# Astavel_and_Monostable_Clock_Circuit_-_2.net
KiCad netlist of a schematic drawn in Altium Designer
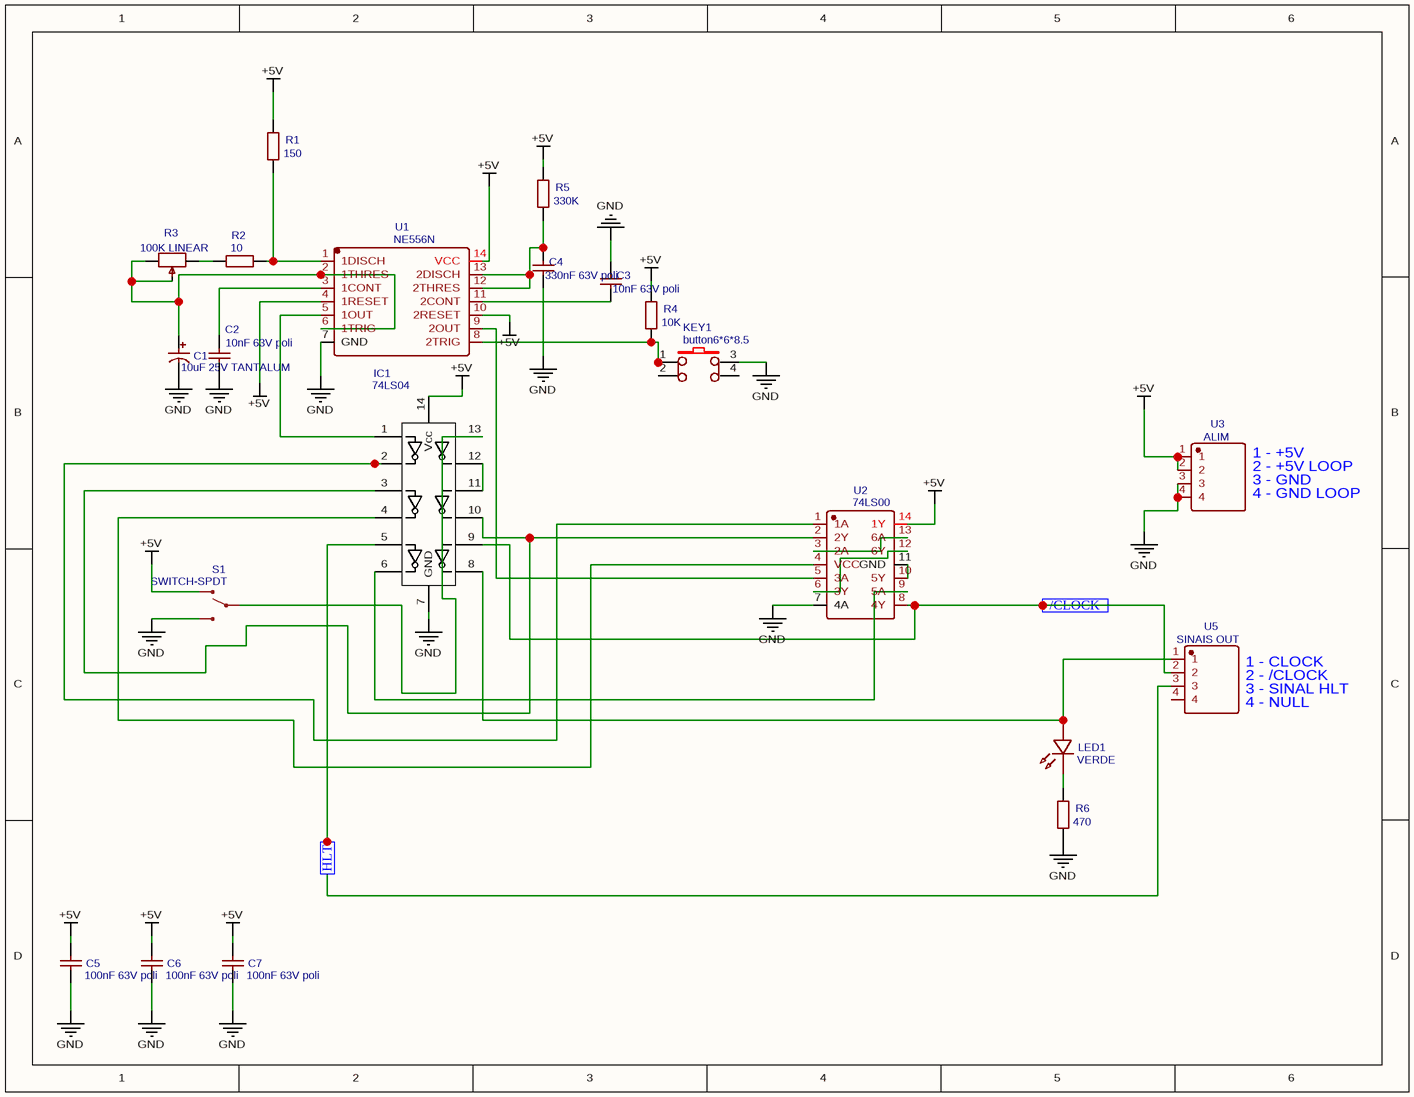
[diagram p0: Astavel and Monostable Clock Circuit - 2.0_2021-10-20.schdoc]

(export (version "E")
  (design (tool "Eeschema 10.0.6"))
  (components
    (comp (ref "C1")
      (value "10uF 25V TANTALUM")
      (fields
        (field (name "BOM_MANUFACTURER PART") "SK100M035B070A")
        (field (name "BOM_SUPPLIER PART") "C62931")
      )
      (libsource (lib "altium-import") (part "root_3_10uF 25V TANTALUM_"))
    )
    (comp (ref "C2")
      (value "10nF 63V poli")
      (fields
        (field (name "BOM_MANUFACTURER PART") "0.01uF(103) 100V")
        (field (name "BOM_SUPPLIER PART") "C10722")
      )
      (libsource (lib "altium-import") (part "root_3_10nF 63V poli_"))
    )
    (comp (ref "C3")
      (value "10nF 63V poli")
      (fields
        (field (name "BOM_MANUFACTURER PART") "0.01uF(103) 100V")
        (field (name "BOM_SUPPLIER PART") "C10722")
      )
      (libsource (lib "altium-import") (part "root_3_10nF 63V poli_"))
    )
    (comp (ref "C4")
      (value "330nF 63V poli")
      (fields
        (field (name "BOM_MANUFACTURER PART") "0.01uF(103) 100V")
        (field (name "BOM_SUPPLIER PART") "C10722")
      )
      (libsource (lib "altium-import") (part "root_3_330nF 63V poli_"))
    )
    (comp (ref "C5")
      (value "100nF 63V poli")
      (fields
        (field (name "BOM_MANUFACTURER PART") "0.01uF(103) 100V")
        (field (name "BOM_SUPPLIER PART") "C10722")
      )
      (libsource (lib "altium-import") (part "root_3_100nF 63V poli_"))
    )
    (comp (ref "C6")
      (value "100nF 63V poli")
      (fields
        (field (name "BOM_MANUFACTURER PART") "0.01uF(103) 100V")
        (field (name "BOM_SUPPLIER PART") "C10722")
      )
      (libsource (lib "altium-import") (part "root_3_100nF 63V poli_"))
    )
    (comp (ref "C7")
      (value "100nF 63V poli")
      (fields
        (field (name "BOM_MANUFACTURER PART") "0.01uF(103) 100V")
        (field (name "BOM_SUPPLIER PART") "C10722")
      )
      (libsource (lib "altium-import") (part "root_3_100nF 63V poli_"))
    )
    (comp (ref "IC1")
      (value "74LS04")
      (fields (field (name "CONTRIBUTOR") "keyboardjunkie"))
      (libsource (lib "altium-import") (part "root_0_74LS04_"))
    )
    (comp (ref "KEY1")
      (value "button6*6*8.5")
      (fields (field (name "BOM_SUPPLIER PART") "C59980"))
      (libsource (lib "altium-import") (part "root_0_button6*6*8.5_"))
    )
    (comp (ref "LED1")
      (value "VERDE")
      (fields
        (field (name "BOM_SUPPLIER PART") "C605465")
        (field (name "BOM_MANUFACTURER PART") "264-7GD")
        (field (name "CONTRIBUTOR") "LCSC")
      )
      (libsource (lib "altium-import") (part "root_1_VERDE_"))
    )
    (comp (ref "R1")
      (value "150")
      (fields (field (name "BOM_MANUFACTURER PART") "7501/2w5%") (field (name "BOM_SUPPLIER PART") "C48642"))
      (libsource (lib "altium-import") (part "root_3_150_"))
    )
    (comp (ref "R2")
      (value "10")
      (fields (field (name "BOM_MANUFACTURER PART") "7501/2w5%") (field (name "BOM_SUPPLIER PART") "C48642"))
      (libsource (lib "altium-import") (part "root_2_10_"))
    )
    (comp (ref "R3")
      (value "100K LINEAR")
      (fields
        (field (name "BOM_MANUFACTURER PART") "3362P-1-502LF")
        (field (name "BOM_SUPPLIER PART") "C81260")
      )
      (libsource (lib "altium-import") (part "root_1_100K LINEAR_"))
    )
    (comp (ref "R4")
      (value "10K")
      (fields (field (name "BOM_MANUFACTURER PART") "7501/2w5%") (field (name "BOM_SUPPLIER PART") "C48642"))
      (libsource (lib "altium-import") (part "root_3_10K_"))
    )
    (comp (ref "R5")
      (value "330K")
      (fields (field (name "BOM_MANUFACTURER PART") "7501/2w5%") (field (name "BOM_SUPPLIER PART") "C48642"))
      (libsource (lib "altium-import") (part "root_3_330K_"))
    )
    (comp (ref "R6")
      (value "470")
      (fields (field (name "BOM_MANUFACTURER PART") "7501/2w5%") (field (name "BOM_SUPPLIER PART") "C48642"))
      (libsource (lib "altium-import") (part "root_3_470_"))
    )
    (comp (ref "S1")
      (value "SWITCH-SPDT")
      (fields (field (name "CONTRIBUTOR") "SparkFun"))
      (libsource (lib "altium-import") (part "root_0_SWITCH-SPDT_"))
    )
    (comp (ref "U1")
      (value "NE556N")
      (fields (field (name "BOM_SUPPLIER PART") "C66175"))
      (libsource (lib "altium-import") (part "root_0_NE556N_"))
    )
    (comp (ref "U2")
      (value "74LS00")
      (fields
        (field (name "BOM_SUPPLIER PART") "C513524")
        (field (name "BOM_MANUFACTURER PART") "XD74LS04")
        (field (name "CONTRIBUTOR") "LCSC")
      )
      (libsource (lib "altium-import") (part "root_0_74LS00_"))
    )
    (comp (ref "U3")
      (value "ALIM")
      (fields
        (field (name "BOM_SUPPLIER PART") "C210162")
        (field (name "BOM_MANUFACTURER PART") "171825-4")
        (field (name "CONTRIBUTOR") "LCSC")
      )
      (libsource (lib "altium-import") (part "root_0_ALIM_"))
    )
    (comp (ref "U5")
      (value "SINAIS OUT")
      (fields
        (field (name "BOM_SUPPLIER PART") "C210162")
        (field (name "BOM_MANUFACTURER PART") "171825-4")
        (field (name "CONTRIBUTOR") "LCSC")
      )
      (libsource (lib "altium-import") (part "root_0_SINAIS OUT_"))
    )
  )
  (nets
    (net (code "1") (name "+5V") (class "Default")
      (node (ref "C5") (pin "1") (pinfunction "1_1") (pintype "passive"))
      (node (ref "C6") (pin "1") (pinfunction "1_1") (pintype "passive"))
      (node (ref "C7") (pin "1") (pinfunction "1_1") (pintype "passive"))
      (node (ref "IC1") (pin "14") (pinfunction "Vcc_14") (pintype "passive"))
      (node (ref "R1") (pin "1") (pinfunction "1_1") (pintype "passive"))
      (node (ref "R4") (pin "1") (pinfunction "1_1") (pintype "passive"))
      (node (ref "R5") (pin "1") (pinfunction "1_1") (pintype "passive"))
      (node (ref "S1") (pin "1") (pinfunction "O_1") (pintype "passive"))
      (node (ref "U1") (pin "10") (pinfunction "2RESET_10") (pintype "passive"))
      (node (ref "U1") (pin "14") (pinfunction "VCC_14") (pintype "passive"))
      (node (ref "U1") (pin "4") (pinfunction "1RESET_4") (pintype "passive"))
      (node (ref "U2") (pin "14") (pinfunction "1Y_14") (pintype "passive"))
      (node (ref "U3") (pin "1") (pinfunction "1_1") (pintype "passive"))
      (node (ref "U3") (pin "2") (pinfunction "2_2") (pintype "passive"))
    )
    (net (code "2") (name "/HLT") (class "Default")
      (node (ref "IC1") (pin "5") (pintype "passive"))
      (node (ref "U5") (pin "3") (pinfunction "3_3") (pintype "passive"))
    )
    (net (code "3") (name "/{slash}CLOCK") (class "Default")
      (node (ref "IC1") (pin "9") (pintype "passive"))
      (node (ref "U2") (pin "8") (pinfunction "4Y_8") (pintype "passive"))
      (node (ref "U5") (pin "2") (pinfunction "2_2") (pintype "passive"))
    )
    (net (code "4") (name "GND") (class "Default")
      (node (ref "C1") (pin "2") (pinfunction "2_2") (pintype "passive"))
      (node (ref "C2") (pin "2") (pinfunction "2_2") (pintype "passive"))
      (node (ref "C3") (pin "1") (pinfunction "1_1") (pintype "passive"))
      (node (ref "C4") (pin "2") (pinfunction "2_2") (pintype "passive"))
      (node (ref "C5") (pin "2") (pinfunction "2_2") (pintype "passive"))
      (node (ref "C6") (pin "2") (pinfunction "2_2") (pintype "passive"))
      (node (ref "C7") (pin "2") (pinfunction "2_2") (pintype "passive"))
      (node (ref "IC1") (pin "7") (pinfunction "GND_7") (pintype "passive"))
      (node (ref "KEY1") (pin "3") (pinfunction "3_3") (pintype "passive"))
      (node (ref "R6") (pin "2") (pinfunction "2_2") (pintype "passive"))
      (node (ref "S1") (pin "3") (pinfunction "S_3") (pintype "passive"))
      (node (ref "U1") (pin "7") (pinfunction "GND_7") (pintype "passive"))
      (node (ref "U2") (pin "7") (pinfunction "4A_7") (pintype "passive"))
      (node (ref "U3") (pin "3") (pinfunction "3_3") (pintype "passive"))
      (node (ref "U3") (pin "4") (pinfunction "4_4") (pintype "passive"))
    )
    (net (code "5") (name "Net-(IC1-Pad11)") (class "Default")
      (node (ref "IC1") (pin "11") (pintype "passive"))
      (node (ref "IC1") (pin "12") (pintype "passive"))
    )
    (net (code "6") (name "Net-(LED1-+)") (class "Default")
      (node (ref "IC1") (pin "8") (pintype "passive"))
      (node (ref "LED1") (pin "2") (pinfunction "+_2") (pintype "passive"))
      (node (ref "U5") (pin "1") (pinfunction "1_1") (pintype "passive"))
    )
    (net (code "7") (name "Net-(LED1--)") (class "Default")
      (node (ref "LED1") (pin "1") (pinfunction "-_1") (pintype "passive"))
      (node (ref "R6") (pin "1") (pinfunction "1_1") (pintype "passive"))
    )
    (net (code "8") (name "Net-(R2-Pad2)") (class "Default")
      (node (ref "R2") (pin "2") (pinfunction "2_2") (pintype "passive"))
      (node (ref "R3") (pin "3") (pinfunction "3_3") (pintype "passive"))
    )
    (net (code "9") (name "Net-(S1-P)") (class "Default")
      (node (ref "IC1") (pin "13") (pintype "passive"))
      (node (ref "S1") (pin "2") (pinfunction "P_2") (pintype "passive"))
    )
    (net (code "10") (name "Net-(U1-1CONT)") (class "Default")
      (node (ref "C2") (pin "1") (pinfunction "1_1") (pintype "passive"))
      (node (ref "U1") (pin "3") (pinfunction "1CONT_3") (pintype "passive"))
    )
    (net (code "11") (name "Net-(U1-1DISCH)") (class "Default")
      (node (ref "R1") (pin "2") (pinfunction "2_2") (pintype "passive"))
      (node (ref "R2") (pin "1") (pinfunction "1_1") (pintype "passive"))
      (node (ref "U1") (pin "1") (pinfunction "1DISCH_1") (pintype "passive"))
    )
    (net (code "12") (name "Net-(U1-1OUT)") (class "Default")
      (node (ref "IC1") (pin "1") (pintype "passive"))
      (node (ref "U1") (pin "5") (pinfunction "1OUT_5") (pintype "passive"))
    )
    (net (code "13") (name "Net-(U1-1THRES)") (class "Default")
      (node (ref "C1") (pin "1") (pinfunction "1_1") (pintype "passive"))
      (node (ref "R3") (pin "1") (pinfunction "1_1") (pintype "passive"))
      (node (ref "R3") (pin "2") (pinfunction "2_2") (pintype "passive"))
      (node (ref "U1") (pin "2") (pinfunction "1THRES_2") (pintype "passive"))
      (node (ref "U1") (pin "6") (pinfunction "1TRIG_6") (pintype "passive"))
    )
    (net (code "14") (name "Net-(U1-2CONT)") (class "Default")
      (node (ref "C3") (pin "2") (pinfunction "2_2") (pintype "passive"))
      (node (ref "U1") (pin "11") (pinfunction "2CONT_11") (pintype "passive"))
    )
    (net (code "15") (name "Net-(U1-2DISCH)") (class "Default")
      (node (ref "C4") (pin "1") (pinfunction "1_1") (pintype "passive"))
      (node (ref "R5") (pin "2") (pinfunction "2_2") (pintype "passive"))
      (node (ref "U1") (pin "12") (pinfunction "2THRES_12") (pintype "passive"))
      (node (ref "U1") (pin "13") (pinfunction "2DISCH_13") (pintype "passive"))
    )
    (net (code "16") (name "Net-(U1-2OUT)") (class "Default")
      (node (ref "U1") (pin "9") (pinfunction "2OUT_9") (pintype "passive"))
      (node (ref "U2") (pin "5") (pinfunction "3A_5") (pintype "passive"))
    )
    (net (code "17") (name "Net-(U1-2TRIG)") (class "Default")
      (node (ref "KEY1") (pin "1") (pinfunction "1_1") (pintype "passive"))
      (node (ref "R4") (pin "2") (pinfunction "2_2") (pintype "passive"))
      (node (ref "U1") (pin "8") (pinfunction "2TRIG_8") (pintype "passive"))
    )
    (net (code "18") (name "Net-(U2-1A)") (class "Default")
      (node (ref "IC1") (pin "2") (pintype "passive"))
      (node (ref "U2") (pin "1") (pinfunction "1A_1") (pintype "passive"))
    )
    (net (code "19") (name "Net-(U2-2A)") (class "Default")
      (node (ref "U2") (pin "13") (pinfunction "6A_13") (pintype "passive"))
      (node (ref "U2") (pin "3") (pinfunction "2A_3") (pintype "passive"))
    )
    (net (code "20") (name "Net-(U2-2Y)") (class "Default")
      (node (ref "IC1") (pin "10") (pintype "passive"))
      (node (ref "IC1") (pin "3") (pintype "passive"))
      (node (ref "U2") (pin "2") (pinfunction "2Y_2") (pintype "passive"))
    )
    (net (code "21") (name "Net-(U2-3Y)") (class "Default")
      (node (ref "U2") (pin "12") (pinfunction "6Y_12") (pintype "passive"))
      (node (ref "U2") (pin "6") (pinfunction "3Y_6") (pintype "passive"))
    )
    (net (code "22") (name "Net-(U2-5A)") (class "Default")
      (node (ref "IC1") (pin "6") (pintype "passive"))
      (node (ref "U2") (pin "9") (pinfunction "5A_9") (pintype "passive"))
    )
    (net (code "23") (name "Net-(U2-5Y)") (class "Default")
      (node (ref "U2") (pin "10") (pinfunction "5Y_10") (pintype "passive"))
      (node (ref "U2") (pin "11") (pinfunction "GND_11") (pintype "passive"))
    )
    (net (code "24") (name "Net-(U2-VCC)") (class "Default")
      (node (ref "IC1") (pin "4") (pintype "passive"))
      (node (ref "U2") (pin "4") (pinfunction "VCC_4") (pintype "passive"))
    )
    (net (code "25") (name "unconnected-(KEY1-Pad2)") (class "Default")
      (node (ref "KEY1") (pin "2") (pinfunction "2_2") (pintype "passive"))
    )
    (net (code "26") (name "unconnected-(KEY1-Pad4)") (class "Default")
      (node (ref "KEY1") (pin "4") (pinfunction "4_4") (pintype "passive"))
    )
    (net (code "27") (name "unconnected-(U5-Pad4)") (class "Default")
      (node (ref "U5") (pin "4") (pinfunction "4_4") (pintype "passive"))
    )
  )
)
